# MAX3232_Breakout.net
KiCad netlist of a schematic drawn in EAGLE
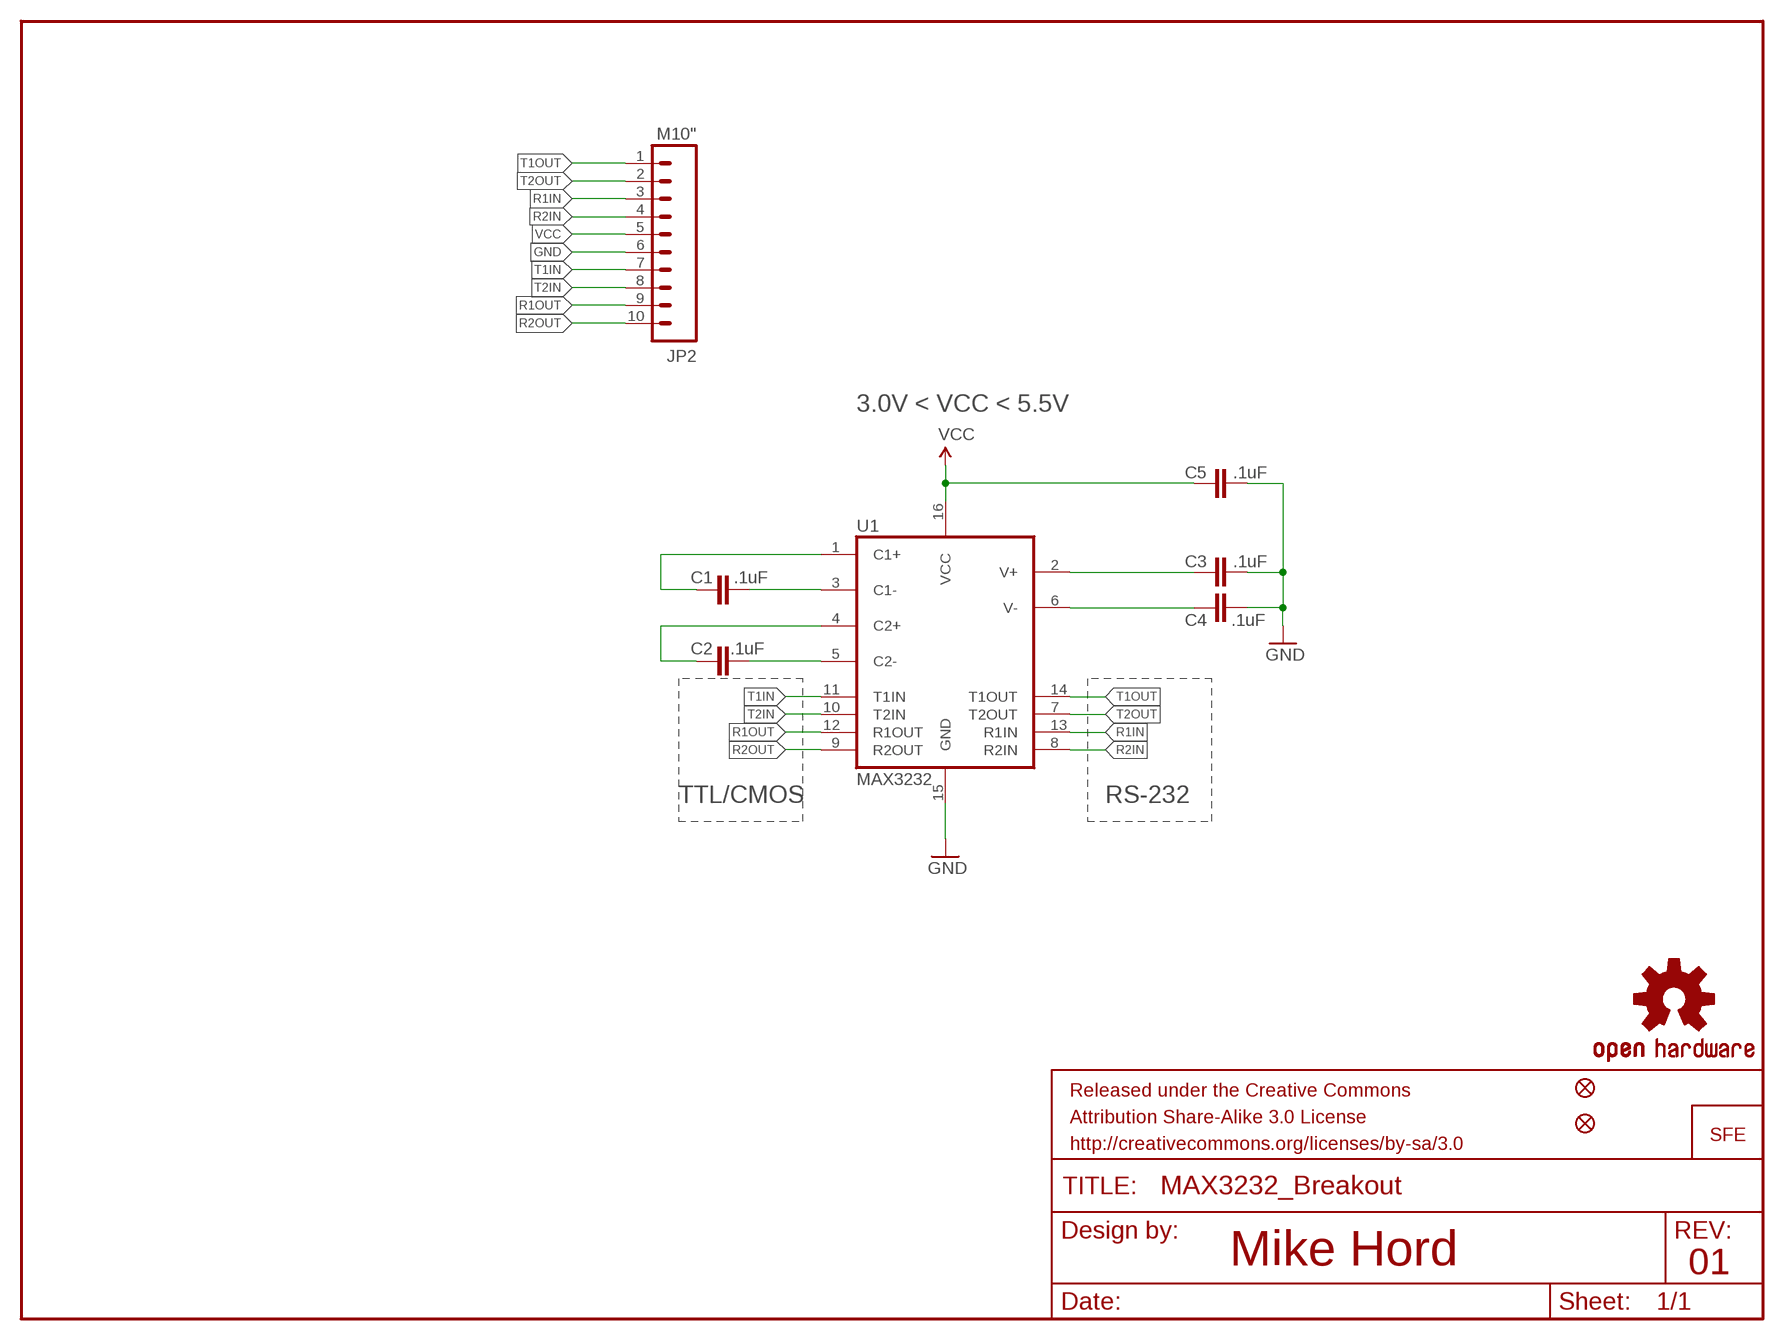
[diagram p0: schematic, sheet 1]

(export (version "E")
  (design (tool "Eeschema 10.0.6"))
  (components
    (comp (ref "C1")
      (value ".1uF")
      (footprint "eagle-import:0402-CAP")
      (libsource (lib "eagle-import") (part "CAP0402-CAP"))
    )
    (comp (ref "C2")
      (value ".1uF")
      (footprint "eagle-import:0402-CAP")
      (libsource (lib "eagle-import") (part "CAP0402-CAP"))
    )
    (comp (ref "C3")
      (value ".1uF")
      (footprint "eagle-import:0402-CAP")
      (libsource (lib "eagle-import") (part "CAP0402-CAP"))
    )
    (comp (ref "C4")
      (value ".1uF")
      (footprint "eagle-import:0402-CAP")
      (libsource (lib "eagle-import") (part "CAP0402-CAP"))
    )
    (comp (ref "C5")
      (value ".1uF")
      (footprint "eagle-import:0402-CAP")
      (libsource (lib "eagle-import") (part "CAP0402-CAP"))
    )
    (comp (ref "FRAME1")
      (value "FRAME-LETTER")
      (footprint "eagle-import:CREATIVE_COMMONS")
      (fields (field (name "NO_PART") "1"))
      (libsource (lib "eagle-import") (part "FRAME-LETTER"))
    )
    (comp (ref "JP1")
      (value "LOGO-SFESK")
      (footprint "eagle-import:SFE-LOGO-FLAME")
      (fields (field (name "NO_PART") "1"))
      (libsource (lib "eagle-import") (part "LOGO-SFESK"))
    )
    (comp (ref "JP2")
      (value "M10\"")
      (footprint "eagle-import:1X10")
      (fields (field (name "NO_PART") "1"))
      (libsource (lib "eagle-import") (part "M10{dblquote}"))
    )
    (comp (ref "JP3")
      (value "FIDUCIALUFIDUCIAL")
      (footprint "eagle-import:MICRO-FIDUCIAL")
      (libsource (lib "eagle-import") (part "FIDUCIALUFIDUCIAL"))
    )
    (comp (ref "JP4")
      (value "FIDUCIALUFIDUCIAL")
      (footprint "eagle-import:MICRO-FIDUCIAL")
      (libsource (lib "eagle-import") (part "FIDUCIALUFIDUCIAL"))
    )
    (comp (ref "U$1")
      (value "OSHW-LOGOM")
      (footprint "eagle-import:OSHW-LOGO-M")
      (fields (field (name "NO_PART") "1"))
      (libsource (lib "eagle-import") (part "OSHW-LOGOM"))
    )
    (comp (ref "U1")
      (value "MAX3232")
      (footprint "eagle-import:SO016")
      (libsource (lib "eagle-import") (part "MAX232SOIC16"))
    )
  )
  (nets
    (net (code "1") (name "GND") (class "Default")
      (node (ref "C3") (pin "2") (pinfunction "2_2") (pintype "passive"))
      (node (ref "C4") (pin "2") (pinfunction "2_2") (pintype "passive"))
      (node (ref "C5") (pin "2") (pinfunction "2_2") (pintype "passive"))
      (node (ref "JP2") (pin "6") (pinfunction "6_6") (pintype "passive"))
      (node (ref "U1") (pin "15") (pinfunction "GND_15") (pintype "bidirectional"))
    )
    (net (code "2") (name "Net-(U1-C1+)") (class "Default")
      (node (ref "C1") (pin "1") (pinfunction "1_1") (pintype "passive"))
      (node (ref "U1") (pin "1") (pinfunction "C1+_1") (pintype "bidirectional"))
    )
    (net (code "3") (name "Net-(U1-C1-)") (class "Default")
      (node (ref "C1") (pin "2") (pinfunction "2_2") (pintype "passive"))
      (node (ref "U1") (pin "3") (pinfunction "C1-_3") (pintype "bidirectional"))
    )
    (net (code "4") (name "Net-(U1-C2+)") (class "Default")
      (node (ref "C2") (pin "1") (pinfunction "1_1") (pintype "passive"))
      (node (ref "U1") (pin "4") (pinfunction "C2+_4") (pintype "bidirectional"))
    )
    (net (code "5") (name "Net-(U1-C2-)") (class "Default")
      (node (ref "C2") (pin "2") (pinfunction "2_2") (pintype "passive"))
      (node (ref "U1") (pin "5") (pinfunction "C2-_5") (pintype "bidirectional"))
    )
    (net (code "6") (name "Net-(U1-V+)") (class "Default")
      (node (ref "C3") (pin "1") (pinfunction "1_1") (pintype "passive"))
      (node (ref "U1") (pin "2") (pinfunction "V+_2") (pintype "bidirectional"))
    )
    (net (code "7") (name "Net-(U1-V-)") (class "Default")
      (node (ref "C4") (pin "1") (pinfunction "1_1") (pintype "passive"))
      (node (ref "U1") (pin "6") (pinfunction "V-_6") (pintype "bidirectional"))
    )
    (net (code "8") (name "R1IN") (class "Default")
      (node (ref "JP2") (pin "3") (pinfunction "3_3") (pintype "passive"))
      (node (ref "U1") (pin "13") (pinfunction "R1IN_13") (pintype "input"))
    )
    (net (code "9") (name "R1OUT") (class "Default")
      (node (ref "JP2") (pin "9") (pinfunction "9_9") (pintype "passive"))
      (node (ref "U1") (pin "12") (pinfunction "R1OUT_12") (pintype "output"))
    )
    (net (code "10") (name "R2IN") (class "Default")
      (node (ref "JP2") (pin "4") (pinfunction "4_4") (pintype "passive"))
      (node (ref "U1") (pin "8") (pinfunction "R2IN_8") (pintype "input"))
    )
    (net (code "11") (name "R2OUT") (class "Default")
      (node (ref "JP2") (pin "10") (pinfunction "10_10") (pintype "passive"))
      (node (ref "U1") (pin "9") (pinfunction "R2OUT_9") (pintype "output"))
    )
    (net (code "12") (name "T1IN") (class "Default")
      (node (ref "JP2") (pin "7") (pinfunction "7_7") (pintype "passive"))
      (node (ref "U1") (pin "11") (pinfunction "T1IN_11") (pintype "input"))
    )
    (net (code "13") (name "T1OUT") (class "Default")
      (node (ref "JP2") (pin "1") (pinfunction "1_1") (pintype "passive"))
      (node (ref "U1") (pin "14") (pinfunction "T1OUT_14") (pintype "output"))
    )
    (net (code "14") (name "T2IN") (class "Default")
      (node (ref "JP2") (pin "8") (pinfunction "8_8") (pintype "passive"))
      (node (ref "U1") (pin "10") (pinfunction "T2IN_10") (pintype "input"))
    )
    (net (code "15") (name "T2OUT") (class "Default")
      (node (ref "JP2") (pin "2") (pinfunction "2_2") (pintype "passive"))
      (node (ref "U1") (pin "7") (pinfunction "T2OUT_7") (pintype "output"))
    )
    (net (code "16") (name "VCC") (class "Default")
      (node (ref "C5") (pin "1") (pinfunction "1_1") (pintype "passive"))
      (node (ref "JP2") (pin "5") (pinfunction "5_5") (pintype "passive"))
      (node (ref "U1") (pin "16") (pinfunction "VCC_16") (pintype "bidirectional"))
    )
  )
)
